# Narrow_GPS_Board_for_Radio.net
KiCad netlist of a schematic drawn in EAGLE
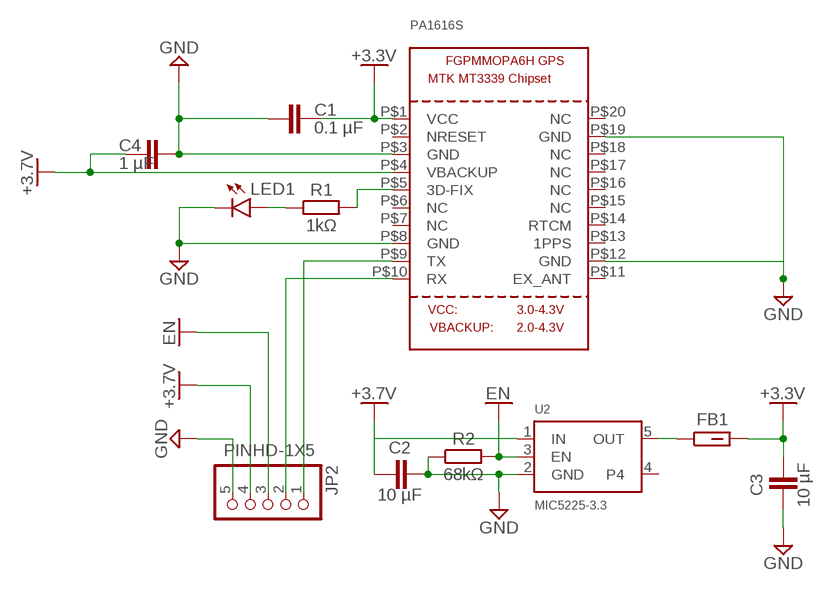
[diagram p0: schematic, sheet 1]

(export (version "E")
  (design (tool "Eeschema 10.0.6"))
  (components
    (comp (ref "C1")
      (value "0.1 µF")
      (footprint "eagle-import:0805")
      (libsource (lib "eagle-import") (part "CAP-0805"))
    )
    (comp (ref "C2")
      (value "10 µF")
      (footprint "eagle-import:0805")
      (libsource (lib "eagle-import") (part "CAP-0805"))
    )
    (comp (ref "C3")
      (value "10 µF")
      (footprint "eagle-import:0805")
      (libsource (lib "eagle-import") (part "CAP-0805"))
    )
    (comp (ref "C4")
      (value "1 µF")
      (footprint "eagle-import:0805")
      (libsource (lib "eagle-import") (part "CAP-0805"))
    )
    (comp (ref "FB1")
      (value "600 Ohms @ 100 MHz")
      (footprint "eagle-import:BEADC2012X105N")
      (libsource (lib "eagle-import") (part "FBCHIP-0805(2012-METRIC)"))
    )
    (comp (ref "JP2")
      (value "PINHD-1X5")
      (footprint "eagle-import:1X05")
      (fields (field (name "MANUFACTURER") "Generic"))
      (libsource (lib "eagle-import") (part "PINHD-1X5"))
    )
    (comp (ref "LED1")
      (value "LED_RED")
      (footprint "eagle-import:LEDC2012X110N_FLAT-R")
      (libsource (lib "eagle-import") (part "CHIP-FLAT-R_0805"))
    )
    (comp (ref "PA1616S")
      (value "GPS_FGPMMOPA6H")
      (footprint "eagle-import:FGPMMOPA6H")
      (libsource (lib "eagle-import") (part "GPS_FGPMMOPA6H"))
    )
    (comp (ref "R1")
      (value "1kΩ")
      (footprint "eagle-import:RESC2012X65")
      (libsource (lib "eagle-import") (part "RCHIP-0805(2012-METRIC)_"))
    )
    (comp (ref "R2")
      (value "68kΩ")
      (footprint "eagle-import:RESC2012X65")
      (libsource (lib "eagle-import") (part "RCHIP-0805(2012-METRIC)_"))
    )
    (comp (ref "U2")
      (value "MIC5225-3.3")
      (footprint "eagle-import:SOT23-5")
      (libsource (lib "eagle-import") (part "VREG_SOT23-5"))
    )
  )
  (nets
    (net (code "1") (name "+3.3V") (class "Default")
      (node (ref "C1") (pin "1") (pinfunction "1_1") (pintype "passive"))
      (node (ref "C3") (pin "2") (pinfunction "2_2") (pintype "passive"))
      (node (ref "FB1") (pin "2") (pinfunction "2_2") (pintype "passive"))
      (node (ref "PA1616S") (pin "P$1") (pinfunction "VCC_P$1") (pintype "bidirectional"))
    )
    (net (code "2") (name "+3.7V") (class "Default")
      (node (ref "C2") (pin "1") (pinfunction "1_1") (pintype "passive"))
      (node (ref "C4") (pin "2") (pinfunction "2_2") (pintype "passive"))
      (node (ref "JP2") (pin "4") (pinfunction "4_4") (pintype "passive"))
      (node (ref "PA1616S") (pin "P$4") (pinfunction "VBACKUP_P$4") (pintype "bidirectional"))
      (node (ref "U2") (pin "1") (pinfunction "IN_1") (pintype "power_in"))
    )
    (net (code "3") (name "EN") (class "Default")
      (node (ref "JP2") (pin "3") (pinfunction "3_3") (pintype "passive"))
      (node (ref "R2") (pin "2") (pinfunction "2_2") (pintype "passive"))
      (node (ref "U2") (pin "3") (pinfunction "EN_3") (pintype "input"))
    )
    (net (code "4") (name "GND") (class "Default")
      (node (ref "C1") (pin "2") (pinfunction "2_2") (pintype "passive"))
      (node (ref "C2") (pin "2") (pinfunction "2_2") (pintype "passive"))
      (node (ref "C3") (pin "1") (pinfunction "1_1") (pintype "passive"))
      (node (ref "C4") (pin "1") (pinfunction "1_1") (pintype "passive"))
      (node (ref "JP2") (pin "5") (pinfunction "5_5") (pintype "passive"))
      (node (ref "LED1") (pin "C") (pinfunction "C_C") (pintype "passive"))
      (node (ref "PA1616S") (pin "P$12") (pinfunction "GND_P$12") (pintype "bidirectional"))
      (node (ref "PA1616S") (pin "P$19") (pinfunction "GND_P$19") (pintype "bidirectional"))
      (node (ref "PA1616S") (pin "P$3") (pinfunction "GND_P$3") (pintype "bidirectional"))
      (node (ref "PA1616S") (pin "P$8") (pinfunction "GND_P$8") (pintype "bidirectional"))
      (node (ref "R2") (pin "1") (pinfunction "1_1") (pintype "passive"))
      (node (ref "U2") (pin "2") (pinfunction "GND_2") (pintype "power_in"))
    )
    (net (code "5") (name "Net-(LED1-PadA)") (class "Default")
      (node (ref "LED1") (pin "A") (pinfunction "A_A") (pintype "passive"))
      (node (ref "R1") (pin "1") (pinfunction "1_1") (pintype "passive"))
    )
    (net (code "6") (name "Net-(PA1616S-3D-FIX)") (class "Default")
      (node (ref "PA1616S") (pin "P$5") (pinfunction "3D-FIX_P$5") (pintype "bidirectional"))
      (node (ref "R1") (pin "2") (pinfunction "2_2") (pintype "passive"))
    )
    (net (code "7") (name "Net-(PA1616S-RX)") (class "Default")
      (node (ref "JP2") (pin "2") (pinfunction "2_2") (pintype "passive"))
      (node (ref "PA1616S") (pin "P$10") (pinfunction "RX_P$10") (pintype "bidirectional"))
    )
    (net (code "8") (name "Net-(PA1616S-TX)") (class "Default")
      (node (ref "JP2") (pin "1") (pinfunction "1_1") (pintype "passive"))
      (node (ref "PA1616S") (pin "P$9") (pinfunction "TX_P$9") (pintype "bidirectional"))
    )
    (net (code "9") (name "Net-(U2-OUT)") (class "Default")
      (node (ref "FB1") (pin "1") (pinfunction "1_1") (pintype "passive"))
      (node (ref "U2") (pin "5") (pinfunction "OUT_5") (pintype "power_in"))
    )
    (net (code "10") (name "unconnected-(PA1616S-1PPS-PadP$13)") (class "Default")
      (node (ref "PA1616S") (pin "P$13") (pinfunction "1PPS_P$13") (pintype "bidirectional"))
    )
    (net (code "11") (name "unconnected-(PA1616S-EX_ANT-PadP$11)") (class "Default")
      (node (ref "PA1616S") (pin "P$11") (pinfunction "EX_ANT_P$11") (pintype "bidirectional"))
    )
    (net (code "12") (name "unconnected-(PA1616S-NC-PadP$6)") (class "Default")
      (node (ref "PA1616S") (pin "P$6") (pinfunction "NC_P$6") (pintype "bidirectional"))
    )
    (net (code "13") (name "unconnected-(PA1616S-NC-PadP$7)") (class "Default")
      (node (ref "PA1616S") (pin "P$7") (pinfunction "NC_P$7") (pintype "bidirectional"))
    )
    (net (code "14") (name "unconnected-(PA1616S-NC-PadP$15)") (class "Default")
      (node (ref "PA1616S") (pin "P$15") (pinfunction "NC_P$15") (pintype "bidirectional"))
    )
    (net (code "15") (name "unconnected-(PA1616S-NC-PadP$16)") (class "Default")
      (node (ref "PA1616S") (pin "P$16") (pinfunction "NC_P$16") (pintype "bidirectional"))
    )
    (net (code "16") (name "unconnected-(PA1616S-NC-PadP$17)") (class "Default")
      (node (ref "PA1616S") (pin "P$17") (pinfunction "NC_P$17") (pintype "bidirectional"))
    )
    (net (code "17") (name "unconnected-(PA1616S-NC-PadP$18)") (class "Default")
      (node (ref "PA1616S") (pin "P$18") (pinfunction "NC_P$18") (pintype "bidirectional"))
    )
    (net (code "18") (name "unconnected-(PA1616S-NC-PadP$20)") (class "Default")
      (node (ref "PA1616S") (pin "P$20") (pinfunction "NC_P$20") (pintype "bidirectional"))
    )
    (net (code "19") (name "unconnected-(PA1616S-NRESET-PadP$2)") (class "Default")
      (node (ref "PA1616S") (pin "P$2") (pinfunction "NRESET_P$2") (pintype "bidirectional"))
    )
    (net (code "20") (name "unconnected-(PA1616S-RTCM-PadP$14)") (class "Default")
      (node (ref "PA1616S") (pin "P$14") (pinfunction "RTCM_P$14") (pintype "bidirectional"))
    )
    (net (code "21") (name "unconnected-(U2-P4-Pad4)") (class "Default")
      (node (ref "U2") (pin "4") (pinfunction "P4_4") (pintype "bidirectional"))
    )
  )
)
